# project1.net
KiCad netlist of a schematic drawn in Altium Designer
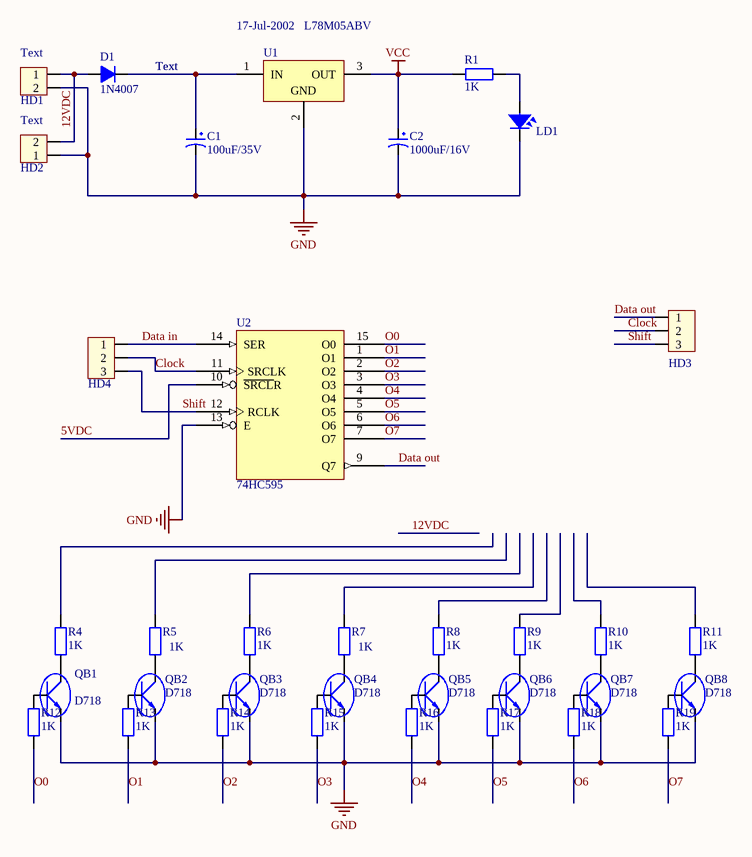
[diagram p0: project1.SchDoc]

(export (version "E")
  (design (tool "Eeschema 10.0.6"))
  (components
    (comp (ref "C1")
      (value "100uF/35V")
      (footprint "6-0805_N")
      (description "Cap 100uF/35V - 470uF/16V")
      (libsource (lib "PART") (part "CP3"))
    )
    (comp (ref "C2")
      (value "1000uF/16V")
      (footprint "6-0805_N")
      (description "Cap 1000uF/16V - 220uF/50V")
      (libsource (lib "PART") (part "CP4"))
    )
    (comp (ref "D1")
      (value "1N4007")
      (footprint "DIODE_SMC")
      (description "Diode 1A")
      (libsource (lib "PART") (part "D1A"))
    )
    (comp (ref "HD1")
      (value "Header 2")
      (footprint "JP2")
      (description "Header 2 (Green)")
      (libsource (lib "") (part "Hed 2_1"))
    )
    (comp (ref "HD2")
      (value "Header 2")
      (footprint "JP2")
      (description "Header 2 (Green)")
      (libsource (lib "PART") (part "Hed 2"))
    )
    (comp (ref "HD3")
      (value "Header 3")
      (footprint "JP3")
      (description "Header 3 (Green)")
      (libsource (lib "") (part "Hed 3_1"))
    )
    (comp (ref "HD4")
      (value "Header 3")
      (footprint "JP3")
      (description "Header 3 (Green)")
      (libsource (lib "PART") (part "Hed 3"))
    )
    (comp (ref "LD1")
      (value "LED")
      (footprint "6-0805_N")
      (description "LED Single colour Green and Red")
      (libsource (lib "PART") (part "LED"))
    )
    (comp (ref "QB1")
      (value "D718")
      (footprint "SOT223-4N")
      (description "Transistor Power Supply")
      (libsource (lib "PART") (part "D718"))
    )
    (comp (ref "QB2")
      (value "D718")
      (footprint "SOT223-4N")
      (description "Transistor Power Supply")
      (libsource (lib "PART") (part "D718"))
    )
    (comp (ref "QB3")
      (value "D718")
      (footprint "SOT223-4N")
      (description "Transistor Power Supply")
      (libsource (lib "PART") (part "D718"))
    )
    (comp (ref "QB4")
      (value "D718")
      (footprint "SOT223-4N")
      (description "Transistor Power Supply")
      (libsource (lib "PART") (part "D718"))
    )
    (comp (ref "QB5")
      (value "D718")
      (footprint "SOT223-4N")
      (description "Transistor Power Supply")
      (libsource (lib "PART") (part "D718"))
    )
    (comp (ref "QB6")
      (value "D718")
      (footprint "SOT223-4N")
      (description "Transistor Power Supply")
      (libsource (lib "PART") (part "D718"))
    )
    (comp (ref "QB7")
      (value "D718")
      (footprint "SOT223-4N")
      (description "Transistor Power Supply")
      (libsource (lib "PART") (part "D718"))
    )
    (comp (ref "QB8")
      (value "D718")
      (footprint "SOT223-4N")
      (description "Transistor Power Supply")
      (libsource (lib "PART") (part "D718"))
    )
    (comp (ref "R1")
      (value "1K")
      (footprint "6-0805_N")
      (description "Resistor 1/4W")
      (libsource (lib "PART") (part "R1/4W"))
    )
    (comp (ref "R4")
      (value "1K")
      (footprint "6-0805_N")
      (description "Resistor 1/4W")
      (libsource (lib "PART") (part "R1/4W"))
    )
    (comp (ref "R5")
      (value "1K")
      (footprint "6-0805_N")
      (description "Resistor 1/4W")
      (libsource (lib "PART") (part "R1/4W"))
    )
    (comp (ref "R6")
      (value "1K")
      (footprint "6-0805_N")
      (description "Resistor 1/4W")
      (libsource (lib "PART") (part "R1/4W"))
    )
    (comp (ref "R7")
      (value "1K")
      (footprint "6-0805_N")
      (description "Resistor 1/4W")
      (libsource (lib "PART") (part "R1/4W"))
    )
    (comp (ref "R8")
      (value "1K")
      (footprint "6-0805_N")
      (description "Resistor 1/4W")
      (libsource (lib "PART") (part "R1/4W"))
    )
    (comp (ref "R9")
      (value "1K")
      (footprint "6-0805_N")
      (description "Resistor 1/4W")
      (libsource (lib "PART") (part "R1/4W"))
    )
    (comp (ref "R10")
      (value "1K")
      (footprint "6-0805_N")
      (description "Resistor 1/4W")
      (libsource (lib "PART") (part "R1/4W"))
    )
    (comp (ref "R11")
      (value "1K")
      (footprint "6-0805_N")
      (description "Resistor 1/4W")
      (libsource (lib "PART") (part "R1/4W"))
    )
    (comp (ref "R12")
      (value "1K")
      (footprint "6-0805_N")
      (description "Resistor 1/4W")
      (libsource (lib "project1") (part "R1/4W"))
    )
    (comp (ref "R13")
      (value "1K")
      (footprint "6-0805_N")
      (description "Resistor 1/4W")
      (libsource (lib "project1") (part "R1/4W"))
    )
    (comp (ref "R14")
      (value "1K")
      (footprint "6-0805_N")
      (description "Resistor 1/4W")
      (libsource (lib "project1") (part "R1/4W"))
    )
    (comp (ref "R15")
      (value "1K")
      (footprint "6-0805_N")
      (description "Resistor 1/4W")
      (libsource (lib "project1") (part "R1/4W"))
    )
    (comp (ref "R16")
      (value "1K")
      (footprint "6-0805_N")
      (description "Resistor 1/4W")
      (libsource (lib "project1") (part "R1/4W"))
    )
    (comp (ref "R17")
      (value "1K")
      (footprint "6-0805_N")
      (description "Resistor 1/4W")
      (libsource (lib "project1") (part "R1/4W"))
    )
    (comp (ref "R18")
      (value "1K")
      (footprint "6-0805_N")
      (description "Resistor 1/4W")
      (libsource (lib "project1") (part "R1/4W"))
    )
    (comp (ref "R19")
      (value "1K")
      (footprint "6-0805_N")
      (description "Resistor 1/4W")
      (libsource (lib "project1") (part "R1/4W"))
    )
    (comp (ref "U1")
      (value "L78M05ABV")
      (footprint "SOT89N")
      (description "Precision 500mA Regulator")
      (fields (field (name "LATESTREVISIONDATE") "17-Jul-2002") (field (name "PUBLISHER") "Altium Limited"))
      (libsource (lib "General IC") (part "L78M05ABV"))
    )
    (comp (ref "U2")
      (value "74HC595")
      (footprint "so16")
      (libsource (lib "Protel DOS Schematic Libraries") (part "74HC595"))
    )
  )
  (nets
    (net (code "1") (name "/5VDC") (class "Default")
      (node (ref "U2") (pin "10") (pinfunction "~{SRCL}R_10") (pintype "input"))
    )
    (net (code "2") (name "/12VDC") (class "Default")
      (node (ref "D1") (pin "1") (pinfunction "A_1") (pintype "passive"))
      (node (ref "HD1") (pin "1") (pinfunction "1_1") (pintype "passive"))
      (node (ref "HD2") (pin "2") (pinfunction "2_2") (pintype "passive"))
    )
    (net (code "3") (name "/Clock") (class "Default")
      (node (ref "HD3") (pin "2") (pinfunction "2_2") (pintype "passive"))
      (node (ref "HD4") (pin "2") (pinfunction "2_2") (pintype "passive"))
      (node (ref "U2") (pin "11") (pinfunction "SRCLK_11") (pintype "input"))
    )
    (net (code "4") (name "/Data in") (class "Default")
      (node (ref "HD4") (pin "1") (pinfunction "1_1") (pintype "passive"))
      (node (ref "U2") (pin "14") (pinfunction "SER_14") (pintype "input"))
    )
    (net (code "5") (name "/Data out") (class "Default")
      (node (ref "HD3") (pin "1") (pinfunction "1_1") (pintype "passive"))
      (node (ref "U2") (pin "9") (pinfunction "Q7_9") (pintype "output"))
    )
    (net (code "6") (name "/O0") (class "Default")
      (node (ref "R12") (pin "1") (pinfunction "1_1") (pintype "passive"))
      (node (ref "U2") (pin "15") (pinfunction "O0_15") (pintype "tri_state"))
    )
    (net (code "7") (name "/O1") (class "Default")
      (node (ref "R13") (pin "1") (pinfunction "1_1") (pintype "passive"))
      (node (ref "U2") (pin "1") (pinfunction "O1_1") (pintype "tri_state"))
    )
    (net (code "8") (name "/O2") (class "Default")
      (node (ref "R14") (pin "1") (pinfunction "1_1") (pintype "passive"))
      (node (ref "U2") (pin "2") (pinfunction "O2_2") (pintype "tri_state"))
    )
    (net (code "9") (name "/O3") (class "Default")
      (node (ref "R15") (pin "1") (pinfunction "1_1") (pintype "passive"))
      (node (ref "U2") (pin "3") (pinfunction "O3_3") (pintype "tri_state"))
    )
    (net (code "10") (name "/O4") (class "Default")
      (node (ref "R16") (pin "1") (pinfunction "1_1") (pintype "passive"))
      (node (ref "U2") (pin "4") (pinfunction "O4_4") (pintype "tri_state"))
    )
    (net (code "11") (name "/O5") (class "Default")
      (node (ref "R17") (pin "1") (pinfunction "1_1") (pintype "passive"))
      (node (ref "U2") (pin "5") (pinfunction "O5_5") (pintype "tri_state"))
    )
    (net (code "12") (name "/O6") (class "Default")
      (node (ref "R18") (pin "1") (pinfunction "1_1") (pintype "passive"))
      (node (ref "U2") (pin "6") (pinfunction "O6_6") (pintype "tri_state"))
    )
    (net (code "13") (name "/O7") (class "Default")
      (node (ref "R19") (pin "1") (pinfunction "1_1") (pintype "passive"))
      (node (ref "U2") (pin "7") (pinfunction "O7_7") (pintype "tri_state"))
    )
    (net (code "14") (name "/Shift") (class "Default")
      (node (ref "HD3") (pin "3") (pinfunction "3_3") (pintype "passive"))
      (node (ref "HD4") (pin "3") (pinfunction "3_3") (pintype "passive"))
      (node (ref "U2") (pin "12") (pinfunction "RCLK_12") (pintype "input"))
    )
    (net (code "15") (name "GND") (class "Default")
      (node (ref "C1") (pin "2") (pinfunction "2_2") (pintype "passive"))
      (node (ref "C2") (pin "2") (pinfunction "2_2") (pintype "passive"))
      (node (ref "HD1") (pin "2") (pinfunction "2_2") (pintype "passive"))
      (node (ref "HD2") (pin "1") (pinfunction "1_1") (pintype "passive"))
      (node (ref "LD1") (pin "2") (pinfunction "2_2") (pintype "passive"))
      (node (ref "QB1") (pin "3") (pinfunction "E_3") (pintype "passive"))
      (node (ref "QB2") (pin "3") (pinfunction "E_3") (pintype "passive"))
      (node (ref "QB3") (pin "3") (pinfunction "E_3") (pintype "passive"))
      (node (ref "QB4") (pin "3") (pinfunction "E_3") (pintype "passive"))
      (node (ref "QB5") (pin "3") (pinfunction "E_3") (pintype "passive"))
      (node (ref "QB6") (pin "3") (pinfunction "E_3") (pintype "passive"))
      (node (ref "QB7") (pin "3") (pinfunction "E_3") (pintype "passive"))
      (node (ref "QB8") (pin "3") (pinfunction "E_3") (pintype "passive"))
      (node (ref "U1") (pin "2") (pinfunction "GND_2") (pintype "power_in"))
      (node (ref "U2") (pin "13") (pinfunction "E_13") (pintype "input"))
      (node (ref "U2") (pin "8") (pinfunction "GND_8") (pintype "power_in"))
    )
    (net (code "16") (name "Net-(D1-K)") (class "Default")
      (node (ref "C1") (pin "1") (pinfunction "1_1") (pintype "passive"))
      (node (ref "D1") (pin "2") (pinfunction "K_2") (pintype "passive"))
      (node (ref "U1") (pin "1") (pinfunction "IN_1") (pintype "power_in"))
    )
    (net (code "17") (name "Net-(LD1-Pad1)") (class "Default")
      (node (ref "LD1") (pin "1") (pinfunction "1_1") (pintype "passive"))
      (node (ref "R1") (pin "1") (pinfunction "1_1") (pintype "passive"))
    )
    (net (code "18") (name "Net-(QB1-B)") (class "Default")
      (node (ref "QB1") (pin "1") (pinfunction "B_1") (pintype "passive"))
      (node (ref "R12") (pin "2") (pinfunction "2_2") (pintype "passive"))
    )
    (net (code "19") (name "Net-(QB1-C)") (class "Default")
      (node (ref "QB1") (pin "2") (pinfunction "C_2") (pintype "passive"))
      (node (ref "R4") (pin "1") (pinfunction "1_1") (pintype "passive"))
    )
    (net (code "20") (name "Net-(QB2-B)") (class "Default")
      (node (ref "QB2") (pin "1") (pinfunction "B_1") (pintype "passive"))
      (node (ref "R13") (pin "2") (pinfunction "2_2") (pintype "passive"))
    )
    (net (code "21") (name "Net-(QB2-C)") (class "Default")
      (node (ref "QB2") (pin "2") (pinfunction "C_2") (pintype "passive"))
      (node (ref "R5") (pin "1") (pinfunction "1_1") (pintype "passive"))
    )
    (net (code "22") (name "Net-(QB3-B)") (class "Default")
      (node (ref "QB3") (pin "1") (pinfunction "B_1") (pintype "passive"))
      (node (ref "R14") (pin "2") (pinfunction "2_2") (pintype "passive"))
    )
    (net (code "23") (name "Net-(QB3-C)") (class "Default")
      (node (ref "QB3") (pin "2") (pinfunction "C_2") (pintype "passive"))
      (node (ref "R6") (pin "1") (pinfunction "1_1") (pintype "passive"))
    )
    (net (code "24") (name "Net-(QB4-B)") (class "Default")
      (node (ref "QB4") (pin "1") (pinfunction "B_1") (pintype "passive"))
      (node (ref "R15") (pin "2") (pinfunction "2_2") (pintype "passive"))
    )
    (net (code "25") (name "Net-(QB4-C)") (class "Default")
      (node (ref "QB4") (pin "2") (pinfunction "C_2") (pintype "passive"))
      (node (ref "R7") (pin "1") (pinfunction "1_1") (pintype "passive"))
    )
    (net (code "26") (name "Net-(QB5-B)") (class "Default")
      (node (ref "QB5") (pin "1") (pinfunction "B_1") (pintype "passive"))
      (node (ref "R16") (pin "2") (pinfunction "2_2") (pintype "passive"))
    )
    (net (code "27") (name "Net-(QB5-C)") (class "Default")
      (node (ref "QB5") (pin "2") (pinfunction "C_2") (pintype "passive"))
      (node (ref "R8") (pin "1") (pinfunction "1_1") (pintype "passive"))
    )
    (net (code "28") (name "Net-(QB6-B)") (class "Default")
      (node (ref "QB6") (pin "1") (pinfunction "B_1") (pintype "passive"))
      (node (ref "R17") (pin "2") (pinfunction "2_2") (pintype "passive"))
    )
    (net (code "29") (name "Net-(QB6-C)") (class "Default")
      (node (ref "QB6") (pin "2") (pinfunction "C_2") (pintype "passive"))
      (node (ref "R9") (pin "1") (pinfunction "1_1") (pintype "passive"))
    )
    (net (code "30") (name "Net-(QB7-B)") (class "Default")
      (node (ref "QB7") (pin "1") (pinfunction "B_1") (pintype "passive"))
      (node (ref "R18") (pin "2") (pinfunction "2_2") (pintype "passive"))
    )
    (net (code "31") (name "Net-(QB7-C)") (class "Default")
      (node (ref "QB7") (pin "2") (pinfunction "C_2") (pintype "passive"))
      (node (ref "R10") (pin "1") (pinfunction "1_1") (pintype "passive"))
    )
    (net (code "32") (name "Net-(QB8-B)") (class "Default")
      (node (ref "QB8") (pin "1") (pinfunction "B_1") (pintype "passive"))
      (node (ref "R19") (pin "2") (pinfunction "2_2") (pintype "passive"))
    )
    (net (code "33") (name "Net-(QB8-C)") (class "Default")
      (node (ref "QB8") (pin "2") (pinfunction "C_2") (pintype "passive"))
      (node (ref "R11") (pin "1") (pinfunction "1_1") (pintype "passive"))
    )
    (net (code "34") (name "VCC") (class "Default")
      (node (ref "C2") (pin "1") (pinfunction "1_1") (pintype "passive"))
      (node (ref "R1") (pin "2") (pinfunction "2_2") (pintype "passive"))
      (node (ref "U1") (pin "3") (pinfunction "OUT_3") (pintype "power_in"))
      (node (ref "U2") (pin "16") (pinfunction "VCC_16") (pintype "power_in"))
    )
    (net (code "35") (name "unconnected-(R4-Pad2)") (class "Default")
      (node (ref "R4") (pin "2") (pinfunction "2_2") (pintype "passive"))
    )
    (net (code "36") (name "unconnected-(R5-Pad2)") (class "Default")
      (node (ref "R5") (pin "2") (pinfunction "2_2") (pintype "passive"))
    )
    (net (code "37") (name "unconnected-(R6-Pad2)") (class "Default")
      (node (ref "R6") (pin "2") (pinfunction "2_2") (pintype "passive"))
    )
    (net (code "38") (name "unconnected-(R7-Pad2)") (class "Default")
      (node (ref "R7") (pin "2") (pinfunction "2_2") (pintype "passive"))
    )
    (net (code "39") (name "unconnected-(R8-Pad2)") (class "Default")
      (node (ref "R8") (pin "2") (pinfunction "2_2") (pintype "passive"))
    )
    (net (code "40") (name "unconnected-(R9-Pad2)") (class "Default")
      (node (ref "R9") (pin "2") (pinfunction "2_2") (pintype "passive"))
    )
    (net (code "41") (name "unconnected-(R10-Pad2)") (class "Default")
      (node (ref "R10") (pin "2") (pinfunction "2_2") (pintype "passive"))
    )
    (net (code "42") (name "unconnected-(R11-Pad2)") (class "Default")
      (node (ref "R11") (pin "2") (pinfunction "2_2") (pintype "passive"))
    )
  )
)
